# EtherNet.net
KiCad netlist of a schematic drawn in Altium Designer
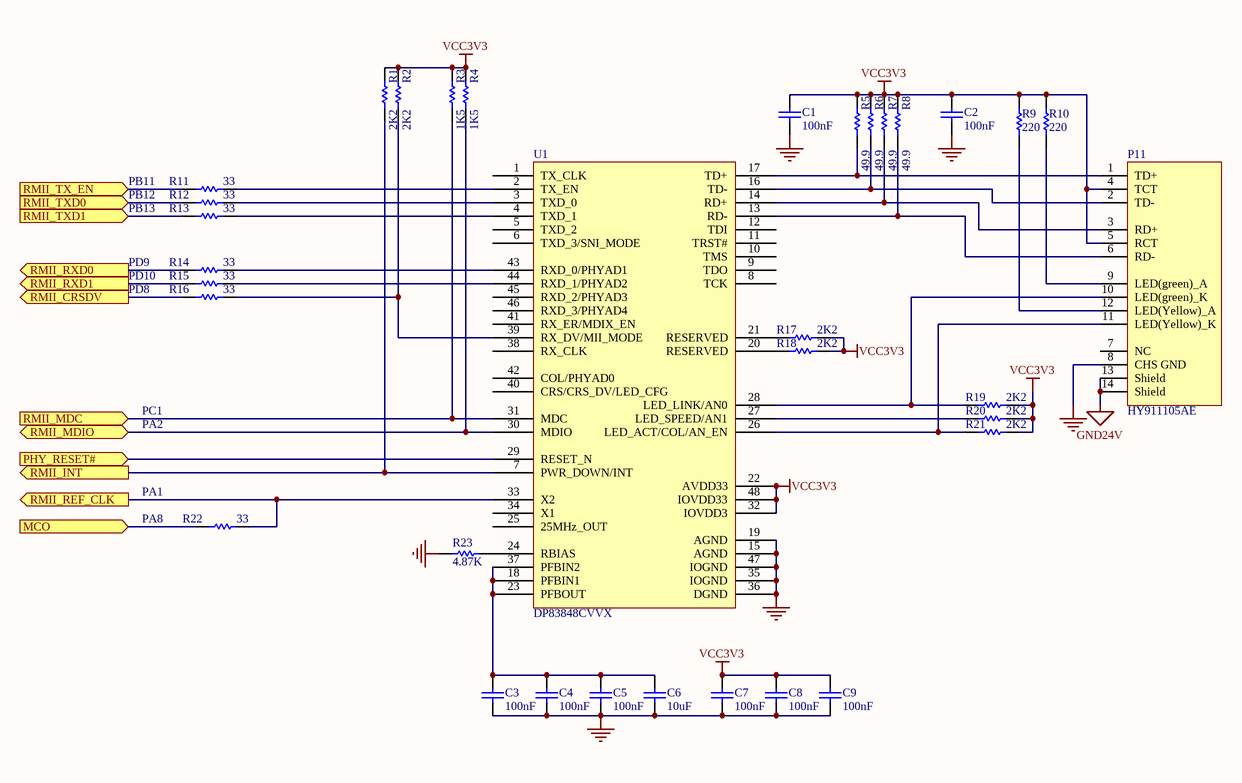
[diagram p0: EtherNet.SchDoc]

(export (version "E")
  (design (tool "Eeschema 10.0.6"))
  (components
    (comp (ref "C1")
      (value "100nF")
      (footprint "0805_C")
      (description "贴片电容")
      (libsource (lib "Miscellaneous Devices LC") (part "0805 100nF(104) 10% 50V"))
    )
    (comp (ref "C2")
      (value "100nF")
      (footprint "0805_C")
      (description "贴片电容")
      (libsource (lib "Miscellaneous Devices LC") (part "0805 100nF(104) 10% 50V"))
    )
    (comp (ref "C3")
      (value "100nF")
      (footprint "0805_C")
      (description "贴片电容")
      (libsource (lib "Miscellaneous Devices LC") (part "0805 100nF(104) 10% 50V"))
    )
    (comp (ref "C4")
      (value "100nF")
      (footprint "0805_C")
      (description "贴片电容")
      (libsource (lib "Miscellaneous Devices LC") (part "0805 100nF(104) 10% 50V"))
    )
    (comp (ref "C5")
      (value "100nF")
      (footprint "0805_C")
      (description "贴片电容")
      (libsource (lib "Miscellaneous Devices LC") (part "0805 100nF(104) 10% 50V"))
    )
    (comp (ref "C6")
      (value "10uF")
      (footprint "0805_C")
      (description "贴片电容")
      (libsource (lib "Miscellaneous Devices LC") (part "0805 10uF (106) 10% 25V"))
    )
    (comp (ref "C7")
      (value "100nF")
      (footprint "0805_C")
      (description "贴片电容")
      (libsource (lib "Miscellaneous Devices LC") (part "0805 100nF(104) 10% 50V"))
    )
    (comp (ref "C8")
      (value "100nF")
      (footprint "0805_C")
      (description "贴片电容")
      (libsource (lib "Miscellaneous Devices LC") (part "0805 100nF(104) 10% 50V"))
    )
    (comp (ref "C9")
      (value "100nF")
      (footprint "0805_C")
      (description "贴片电容")
      (libsource (lib "Miscellaneous Devices LC") (part "0805 100nF(104) 10% 50V"))
    )
    (comp (ref "P11")
      (value "HY911105AE")
      (footprint "HANRUN-A8")
      (libsource (lib "MB784") (part "J0011D21B"))
    )
    (comp (ref "R1")
      (value "2K2")
      (footprint "0805_R")
      (description "Resistor")
      (fields (field (name "PUBLISHER") "Altium Limited"))
      (libsource (lib "Miscellaneous Devices") (part "Res1"))
    )
    (comp (ref "R2")
      (value "2K2")
      (footprint "0805_R")
      (description "Resistor")
      (fields (field (name "PUBLISHER") "Altium Limited"))
      (libsource (lib "Miscellaneous Devices") (part "Res1"))
    )
    (comp (ref "R3")
      (value "1K5")
      (footprint "0805_R")
      (description "Resistor")
      (fields (field (name "PUBLISHER") "Altium Limited"))
      (libsource (lib "Miscellaneous Devices") (part "Res1"))
    )
    (comp (ref "R4")
      (value "1K5")
      (footprint "0805_R")
      (description "Resistor")
      (fields (field (name "PUBLISHER") "Altium Limited"))
      (libsource (lib "Miscellaneous Devices") (part "Res1"))
    )
    (comp (ref "R5")
      (value "49.9")
      (footprint "0805_R")
      (description "Resistor")
      (fields (field (name "PUBLISHER") "Altium Limited"))
      (libsource (lib "Miscellaneous Devices") (part "Res1"))
    )
    (comp (ref "R6")
      (value "49.9")
      (footprint "0805_R")
      (description "Resistor")
      (fields (field (name "PUBLISHER") "Altium Limited"))
      (libsource (lib "Miscellaneous Devices") (part "Res1"))
    )
    (comp (ref "R7")
      (value "49.9")
      (footprint "0805_R")
      (description "Resistor")
      (fields (field (name "PUBLISHER") "Altium Limited"))
      (libsource (lib "Miscellaneous Devices") (part "Res1"))
    )
    (comp (ref "R8")
      (value "49.9")
      (footprint "0805_R")
      (description "Resistor")
      (fields (field (name "PUBLISHER") "Altium Limited"))
      (libsource (lib "Miscellaneous Devices") (part "Res1"))
    )
    (comp (ref "R9")
      (value "220")
      (footprint "0805_R")
      (description "Resistor")
      (fields (field (name "PUBLISHER") "Altium Limited"))
      (libsource (lib "Miscellaneous Devices") (part "Res1"))
    )
    (comp (ref "R10")
      (value "220")
      (footprint "0805_R")
      (description "Resistor")
      (fields (field (name "PUBLISHER") "Altium Limited"))
      (libsource (lib "Miscellaneous Devices") (part "Res1"))
    )
    (comp (ref "R11")
      (value "33")
      (footprint "0805_R")
      (description "Resistor")
      (fields (field (name "PUBLISHER") "Altium Limited"))
      (libsource (lib "Miscellaneous Devices") (part "Res1"))
    )
    (comp (ref "R12")
      (value "33")
      (footprint "0805_R")
      (description "Resistor")
      (fields (field (name "PUBLISHER") "Altium Limited"))
      (libsource (lib "Miscellaneous Devices") (part "Res1"))
    )
    (comp (ref "R13")
      (value "33")
      (footprint "0805_R")
      (description "Resistor")
      (fields (field (name "PUBLISHER") "Altium Limited"))
      (libsource (lib "Miscellaneous Devices") (part "Res1"))
    )
    (comp (ref "R14")
      (value "33")
      (footprint "0805_R")
      (description "Resistor")
      (fields (field (name "PUBLISHER") "Altium Limited"))
      (libsource (lib "Miscellaneous Devices") (part "Res1"))
    )
    (comp (ref "R15")
      (value "33")
      (footprint "0805_R")
      (description "Resistor")
      (fields (field (name "PUBLISHER") "Altium Limited"))
      (libsource (lib "Miscellaneous Devices") (part "Res1"))
    )
    (comp (ref "R16")
      (value "33")
      (footprint "0805_R")
      (description "Resistor")
      (fields (field (name "PUBLISHER") "Altium Limited"))
      (libsource (lib "Miscellaneous Devices") (part "Res1"))
    )
    (comp (ref "R17")
      (value "2K2")
      (footprint "0805_R")
      (description "Resistor")
      (fields (field (name "PUBLISHER") "Altium Limited"))
      (libsource (lib "Miscellaneous Devices") (part "Res1"))
    )
    (comp (ref "R18")
      (value "2K2")
      (footprint "0805_R")
      (description "Resistor")
      (fields (field (name "PUBLISHER") "Altium Limited"))
      (libsource (lib "Miscellaneous Devices") (part "Res1"))
    )
    (comp (ref "R19")
      (value "2K2")
      (footprint "0805_R")
      (description "Resistor")
      (fields (field (name "PUBLISHER") "Altium Limited"))
      (libsource (lib "Miscellaneous Devices") (part "Res1"))
    )
    (comp (ref "R20")
      (value "2K2")
      (footprint "0805_R")
      (description "Resistor")
      (fields (field (name "PUBLISHER") "Altium Limited"))
      (libsource (lib "Miscellaneous Devices") (part "Res1"))
    )
    (comp (ref "R21")
      (value "2K2")
      (footprint "0805_R")
      (description "Resistor")
      (fields (field (name "PUBLISHER") "Altium Limited"))
      (libsource (lib "Miscellaneous Devices") (part "Res1"))
    )
    (comp (ref "R22")
      (value "33")
      (footprint "0805_R")
      (description "Resistor")
      (fields (field (name "PUBLISHER") "Altium Limited"))
      (libsource (lib "Miscellaneous Devices") (part "Res1"))
    )
    (comp (ref "R23")
      (value "4.87K")
      (footprint "0805_R")
      (description "Resistor")
      (fields (field (name "PUBLISHER") "Altium Limited"))
      (libsource (lib "Miscellaneous Devices") (part "Res1"))
    )
    (comp (ref "U1")
      (value "DP83848CVVX")
      (footprint "LQFP-48_7x7x05P")
      (description "接口芯片")
      (libsource (lib "Miscellaneous Devices LC") (part "DP83848CVVX_[C16688]"))
    )
  )
  (nets
    (net (code "1") (name "/MCO") (class "Default")
      (node (ref "R22") (pin "2") (pinfunction "2_2") (pintype "passive"))
    )
    (net (code "2") (name "/PHY_RESET#") (class "Default")
      (node (ref "U1") (pin "29") (pinfunction "RESET_N_29") (pintype "passive"))
    )
    (net (code "3") (name "/RMII_CRSDV") (class "Default")
      (node (ref "R16") (pin "2") (pinfunction "2_2") (pintype "passive"))
    )
    (net (code "4") (name "/RMII_INT") (class "Default")
      (node (ref "R1") (pin "1") (pinfunction "1_1") (pintype "passive"))
      (node (ref "U1") (pin "7") (pinfunction "PWR_DOWN/INT_7") (pintype "passive"))
    )
    (net (code "5") (name "/RMII_MDC") (class "Default")
      (node (ref "R3") (pin "1") (pinfunction "1_1") (pintype "passive"))
      (node (ref "U1") (pin "31") (pinfunction "MDC_31") (pintype "passive"))
    )
    (net (code "6") (name "/RMII_MDIO") (class "Default")
      (node (ref "R4") (pin "1") (pinfunction "1_1") (pintype "passive"))
      (node (ref "U1") (pin "30") (pinfunction "MDIO_30") (pintype "passive"))
    )
    (net (code "7") (name "/RMII_REF_CLK") (class "Default")
      (node (ref "R22") (pin "1") (pinfunction "1_1") (pintype "passive"))
      (node (ref "U1") (pin "33") (pinfunction "X2_33") (pintype "passive"))
    )
    (net (code "8") (name "/RMII_RXD0") (class "Default")
      (node (ref "R14") (pin "2") (pinfunction "2_2") (pintype "passive"))
    )
    (net (code "9") (name "/RMII_RXD1") (class "Default")
      (node (ref "R15") (pin "2") (pinfunction "2_2") (pintype "passive"))
    )
    (net (code "10") (name "/RMII_TXD0") (class "Default")
      (node (ref "R12") (pin "2") (pinfunction "2_2") (pintype "passive"))
    )
    (net (code "11") (name "/RMII_TXD1") (class "Default")
      (node (ref "R13") (pin "2") (pinfunction "2_2") (pintype "passive"))
    )
    (net (code "12") (name "/RMII_TX_EN") (class "Default")
      (node (ref "R11") (pin "2") (pinfunction "2_2") (pintype "passive"))
    )
    (net (code "13") (name "GND") (class "Default")
      (node (ref "C1") (pin "2") (pinfunction "2_2") (pintype "passive"))
      (node (ref "C2") (pin "2") (pinfunction "2_2") (pintype "passive"))
      (node (ref "C3") (pin "2") (pinfunction "2_2") (pintype "passive"))
      (node (ref "C4") (pin "2") (pinfunction "2_2") (pintype "passive"))
      (node (ref "C5") (pin "2") (pinfunction "2_2") (pintype "passive"))
      (node (ref "C6") (pin "1") (pinfunction "1_1") (pintype "passive"))
      (node (ref "C7") (pin "2") (pinfunction "2_2") (pintype "passive"))
      (node (ref "C8") (pin "2") (pinfunction "2_2") (pintype "passive"))
      (node (ref "C9") (pin "2") (pinfunction "2_2") (pintype "passive"))
      (node (ref "P11") (pin "8") (pinfunction "CHS_GND_8") (pintype "passive"))
      (node (ref "R23") (pin "1") (pinfunction "1_1") (pintype "passive"))
      (node (ref "U1") (pin "15") (pinfunction "AGND_15") (pintype "passive"))
      (node (ref "U1") (pin "19") (pinfunction "AGND_19") (pintype "passive"))
      (node (ref "U1") (pin "35") (pinfunction "IOGND_35") (pintype "passive"))
      (node (ref "U1") (pin "36") (pinfunction "DGND_36") (pintype "passive"))
      (node (ref "U1") (pin "47") (pinfunction "IOGND_47") (pintype "passive"))
    )
    (net (code "14") (name "GND24V") (class "Default")
      (node (ref "P11") (pin "13") (pinfunction "Shield_13") (pintype "passive"))
      (node (ref "P11") (pin "14") (pinfunction "Shield_14") (pintype "passive"))
    )
    (net (code "15") (name "Net-(P11-LED(Yellow)_A)") (class "Default")
      (node (ref "P11") (pin "12") (pinfunction "LED(Yellow)_A_12") (pintype "passive"))
      (node (ref "R9") (pin "1") (pinfunction "1_1") (pintype "passive"))
    )
    (net (code "16") (name "Net-(P11-LED(Yellow)_K)") (class "Default")
      (node (ref "P11") (pin "11") (pinfunction "LED(Yellow)_K_11") (pintype "passive"))
      (node (ref "R21") (pin "1") (pinfunction "1_1") (pintype "passive"))
      (node (ref "U1") (pin "26") (pinfunction "LED_ACT/COL/AN_EN_26") (pintype "passive"))
    )
    (net (code "17") (name "Net-(P11-LED(green)_A)") (class "Default")
      (node (ref "P11") (pin "9") (pinfunction "LED(green)_A_9") (pintype "passive"))
      (node (ref "R10") (pin "1") (pinfunction "1_1") (pintype "passive"))
    )
    (net (code "18") (name "Net-(P11-LED(green)_K)") (class "Default")
      (node (ref "P11") (pin "10") (pinfunction "LED(green)_K_10") (pintype "passive"))
      (node (ref "R19") (pin "1") (pinfunction "1_1") (pintype "passive"))
      (node (ref "U1") (pin "28") (pinfunction "LED_LINK/AN0_28") (pintype "passive"))
    )
    (net (code "19") (name "Net-(P11-RD+)") (class "Default")
      (node (ref "P11") (pin "3") (pinfunction "RD+_3") (pintype "passive"))
      (node (ref "R7") (pin "1") (pinfunction "1_1") (pintype "passive"))
      (node (ref "U1") (pin "14") (pinfunction "RD+_14") (pintype "passive"))
    )
    (net (code "20") (name "Net-(P11-RD-)") (class "Default")
      (node (ref "P11") (pin "6") (pinfunction "RD-_6") (pintype "passive"))
      (node (ref "R8") (pin "1") (pinfunction "1_1") (pintype "passive"))
      (node (ref "U1") (pin "13") (pinfunction "RD-_13") (pintype "passive"))
    )
    (net (code "21") (name "Net-(P11-TD+)") (class "Default")
      (node (ref "P11") (pin "1") (pinfunction "TD+_1") (pintype "passive"))
      (node (ref "R5") (pin "1") (pinfunction "1_1") (pintype "passive"))
      (node (ref "U1") (pin "17") (pinfunction "TD+_17") (pintype "passive"))
    )
    (net (code "22") (name "Net-(P11-TD-)") (class "Default")
      (node (ref "P11") (pin "2") (pinfunction "TD-_2") (pintype "passive"))
      (node (ref "R6") (pin "1") (pinfunction "1_1") (pintype "passive"))
      (node (ref "U1") (pin "16") (pinfunction "TD-_16") (pintype "passive"))
    )
    (net (code "23") (name "Net-(R17-Pad1)") (class "Default")
      (node (ref "R17") (pin "1") (pinfunction "1_1") (pintype "passive"))
      (node (ref "U1") (pin "21") (pinfunction "RESERVED_21") (pintype "passive"))
    )
    (net (code "24") (name "Net-(R18-Pad1)") (class "Default")
      (node (ref "R18") (pin "1") (pinfunction "1_1") (pintype "passive"))
      (node (ref "U1") (pin "20") (pinfunction "RESERVED_20") (pintype "passive"))
    )
    (net (code "25") (name "Net-(U1-LED_SPEED{slash}AN1)") (class "Default")
      (node (ref "R20") (pin "1") (pinfunction "1_1") (pintype "passive"))
      (node (ref "U1") (pin "27") (pinfunction "LED_SPEED/AN1_27") (pintype "passive"))
    )
    (net (code "26") (name "Net-(U1-PFBIN1)") (class "Default")
      (node (ref "C3") (pin "1") (pinfunction "1_1") (pintype "passive"))
      (node (ref "C4") (pin "1") (pinfunction "1_1") (pintype "passive"))
      (node (ref "C5") (pin "1") (pinfunction "1_1") (pintype "passive"))
      (node (ref "C6") (pin "2") (pinfunction "2_2") (pintype "passive"))
      (node (ref "U1") (pin "18") (pinfunction "PFBIN1_18") (pintype "passive"))
      (node (ref "U1") (pin "23") (pinfunction "PFBOUT_23") (pintype "passive"))
      (node (ref "U1") (pin "37") (pinfunction "PFBIN2_37") (pintype "passive"))
    )
    (net (code "27") (name "Net-(U1-RBIAS)") (class "Default")
      (node (ref "R23") (pin "2") (pinfunction "2_2") (pintype "passive"))
      (node (ref "U1") (pin "24") (pinfunction "RBIAS_24") (pintype "passive"))
    )
    (net (code "28") (name "Net-(U1-RXD_0{slash}PHYAD1)") (class "Default")
      (node (ref "R14") (pin "1") (pinfunction "1_1") (pintype "passive"))
      (node (ref "U1") (pin "43") (pinfunction "RXD_0/PHYAD1_43") (pintype "passive"))
    )
    (net (code "29") (name "Net-(U1-RXD_1{slash}PHYAD2)") (class "Default")
      (node (ref "R15") (pin "1") (pinfunction "1_1") (pintype "passive"))
      (node (ref "U1") (pin "44") (pinfunction "RXD_1/PHYAD2_44") (pintype "passive"))
    )
    (net (code "30") (name "Net-(U1-RX_DV{slash}MII_MODE)") (class "Default")
      (node (ref "R16") (pin "1") (pinfunction "1_1") (pintype "passive"))
      (node (ref "R2") (pin "1") (pinfunction "1_1") (pintype "passive"))
      (node (ref "U1") (pin "39") (pinfunction "RX_DV/MII_MODE_39") (pintype "passive"))
    )
    (net (code "31") (name "Net-(U1-TXD_0)") (class "Default")
      (node (ref "R12") (pin "1") (pinfunction "1_1") (pintype "passive"))
      (node (ref "U1") (pin "3") (pinfunction "TXD_0_3") (pintype "passive"))
    )
    (net (code "32") (name "Net-(U1-TXD_1)") (class "Default")
      (node (ref "R13") (pin "1") (pinfunction "1_1") (pintype "passive"))
      (node (ref "U1") (pin "4") (pinfunction "TXD_1_4") (pintype "passive"))
    )
    (net (code "33") (name "Net-(U1-TX_EN)") (class "Default")
      (node (ref "R11") (pin "1") (pinfunction "1_1") (pintype "passive"))
      (node (ref "U1") (pin "2") (pinfunction "TX_EN_2") (pintype "passive"))
    )
    (net (code "34") (name "VCC3V3") (class "Default")
      (node (ref "C1") (pin "1") (pinfunction "1_1") (pintype "passive"))
      (node (ref "C2") (pin "1") (pinfunction "1_1") (pintype "passive"))
      (node (ref "C7") (pin "1") (pinfunction "1_1") (pintype "passive"))
      (node (ref "C8") (pin "1") (pinfunction "1_1") (pintype "passive"))
      (node (ref "C9") (pin "1") (pinfunction "1_1") (pintype "passive"))
      (node (ref "P11") (pin "4") (pinfunction "TCT_4") (pintype "passive"))
      (node (ref "P11") (pin "5") (pinfunction "RCT_5") (pintype "passive"))
      (node (ref "R1") (pin "2") (pinfunction "2_2") (pintype "passive"))
      (node (ref "R10") (pin "2") (pinfunction "2_2") (pintype "passive"))
      (node (ref "R17") (pin "2") (pinfunction "2_2") (pintype "passive"))
      (node (ref "R18") (pin "2") (pinfunction "2_2") (pintype "passive"))
      (node (ref "R19") (pin "2") (pinfunction "2_2") (pintype "passive"))
      (node (ref "R2") (pin "2") (pinfunction "2_2") (pintype "passive"))
      (node (ref "R20") (pin "2") (pinfunction "2_2") (pintype "passive"))
      (node (ref "R21") (pin "2") (pinfunction "2_2") (pintype "passive"))
      (node (ref "R3") (pin "2") (pinfunction "2_2") (pintype "passive"))
      (node (ref "R4") (pin "2") (pinfunction "2_2") (pintype "passive"))
      (node (ref "R5") (pin "2") (pinfunction "2_2") (pintype "passive"))
      (node (ref "R6") (pin "2") (pinfunction "2_2") (pintype "passive"))
      (node (ref "R7") (pin "2") (pinfunction "2_2") (pintype "passive"))
      (node (ref "R8") (pin "2") (pinfunction "2_2") (pintype "passive"))
      (node (ref "R9") (pin "2") (pinfunction "2_2") (pintype "passive"))
      (node (ref "U1") (pin "22") (pinfunction "AVDD33_22") (pintype "passive"))
      (node (ref "U1") (pin "32") (pinfunction "IOVDD3_32") (pintype "passive"))
      (node (ref "U1") (pin "48") (pinfunction "IOVDD33_48") (pintype "passive"))
    )
    (net (code "35") (name "unconnected-(P11-NC-Pad7)") (class "Default")
      (node (ref "P11") (pin "7") (pinfunction "NC_7") (pintype "passive"))
    )
    (net (code "36") (name "unconnected-(U1-25MHz_OUT-Pad25)") (class "Default")
      (node (ref "U1") (pin "25") (pinfunction "25MHz_OUT_25") (pintype "passive"))
    )
    (net (code "37") (name "unconnected-(U1-COL{slash}PHYAD0-Pad42)") (class "Default")
      (node (ref "U1") (pin "42") (pinfunction "COL/PHYAD0_42") (pintype "passive"))
    )
    (net (code "38") (name "unconnected-(U1-CRS{slash}CRS_DV{slash}LED_CFG-Pad40)") (class "Default")
      (node (ref "U1") (pin "40") (pinfunction "CRS/CRS_DV/LED_CFG_40") (pintype "passive"))
    )
    (net (code "39") (name "unconnected-(U1-RXD_2{slash}PHYAD3-Pad45)") (class "Default")
      (node (ref "U1") (pin "45") (pinfunction "RXD_2/PHYAD3_45") (pintype "passive"))
    )
    (net (code "40") (name "unconnected-(U1-RXD_3{slash}PHYAD4-Pad46)") (class "Default")
      (node (ref "U1") (pin "46") (pinfunction "RXD_3/PHYAD4_46") (pintype "passive"))
    )
    (net (code "41") (name "unconnected-(U1-RX_CLK-Pad38)") (class "Default")
      (node (ref "U1") (pin "38") (pinfunction "RX_CLK_38") (pintype "passive"))
    )
    (net (code "42") (name "unconnected-(U1-RX_ER{slash}MDIX_EN-Pad41)") (class "Default")
      (node (ref "U1") (pin "41") (pinfunction "RX_ER/MDIX_EN_41") (pintype "passive"))
    )
    (net (code "43") (name "unconnected-(U1-TCK-Pad8)") (class "Default")
      (node (ref "U1") (pin "8") (pinfunction "TCK_8") (pintype "passive"))
    )
    (net (code "44") (name "unconnected-(U1-TDI-Pad12)") (class "Default")
      (node (ref "U1") (pin "12") (pinfunction "TDI_12") (pintype "passive"))
    )
    (net (code "45") (name "unconnected-(U1-TDO-Pad9)") (class "Default")
      (node (ref "U1") (pin "9") (pinfunction "TDO_9") (pintype "passive"))
    )
    (net (code "46") (name "unconnected-(U1-TMS-Pad10)") (class "Default")
      (node (ref "U1") (pin "10") (pinfunction "TMS_10") (pintype "passive"))
    )
    (net (code "47") (name "unconnected-(U1-TRST#-Pad11)") (class "Default")
      (node (ref "U1") (pin "11") (pinfunction "TRST#_11") (pintype "passive"))
    )
    (net (code "48") (name "unconnected-(U1-TXD_2-Pad5)") (class "Default")
      (node (ref "U1") (pin "5") (pinfunction "TXD_2_5") (pintype "passive"))
    )
    (net (code "49") (name "unconnected-(U1-TXD_3{slash}SNI_MODE-Pad6)") (class "Default")
      (node (ref "U1") (pin "6") (pinfunction "TXD_3/SNI_MODE_6") (pintype "passive"))
    )
    (net (code "50") (name "unconnected-(U1-TX_CLK-Pad1)") (class "Default")
      (node (ref "U1") (pin "1") (pinfunction "TX_CLK_1") (pintype "passive"))
    )
    (net (code "51") (name "unconnected-(U1-X1-Pad34)") (class "Default")
      (node (ref "U1") (pin "34") (pinfunction "X1_34") (pintype "passive"))
    )
  )
)
